# pcie2usbc.net
KiCad netlist of a schematic drawn in EAGLE
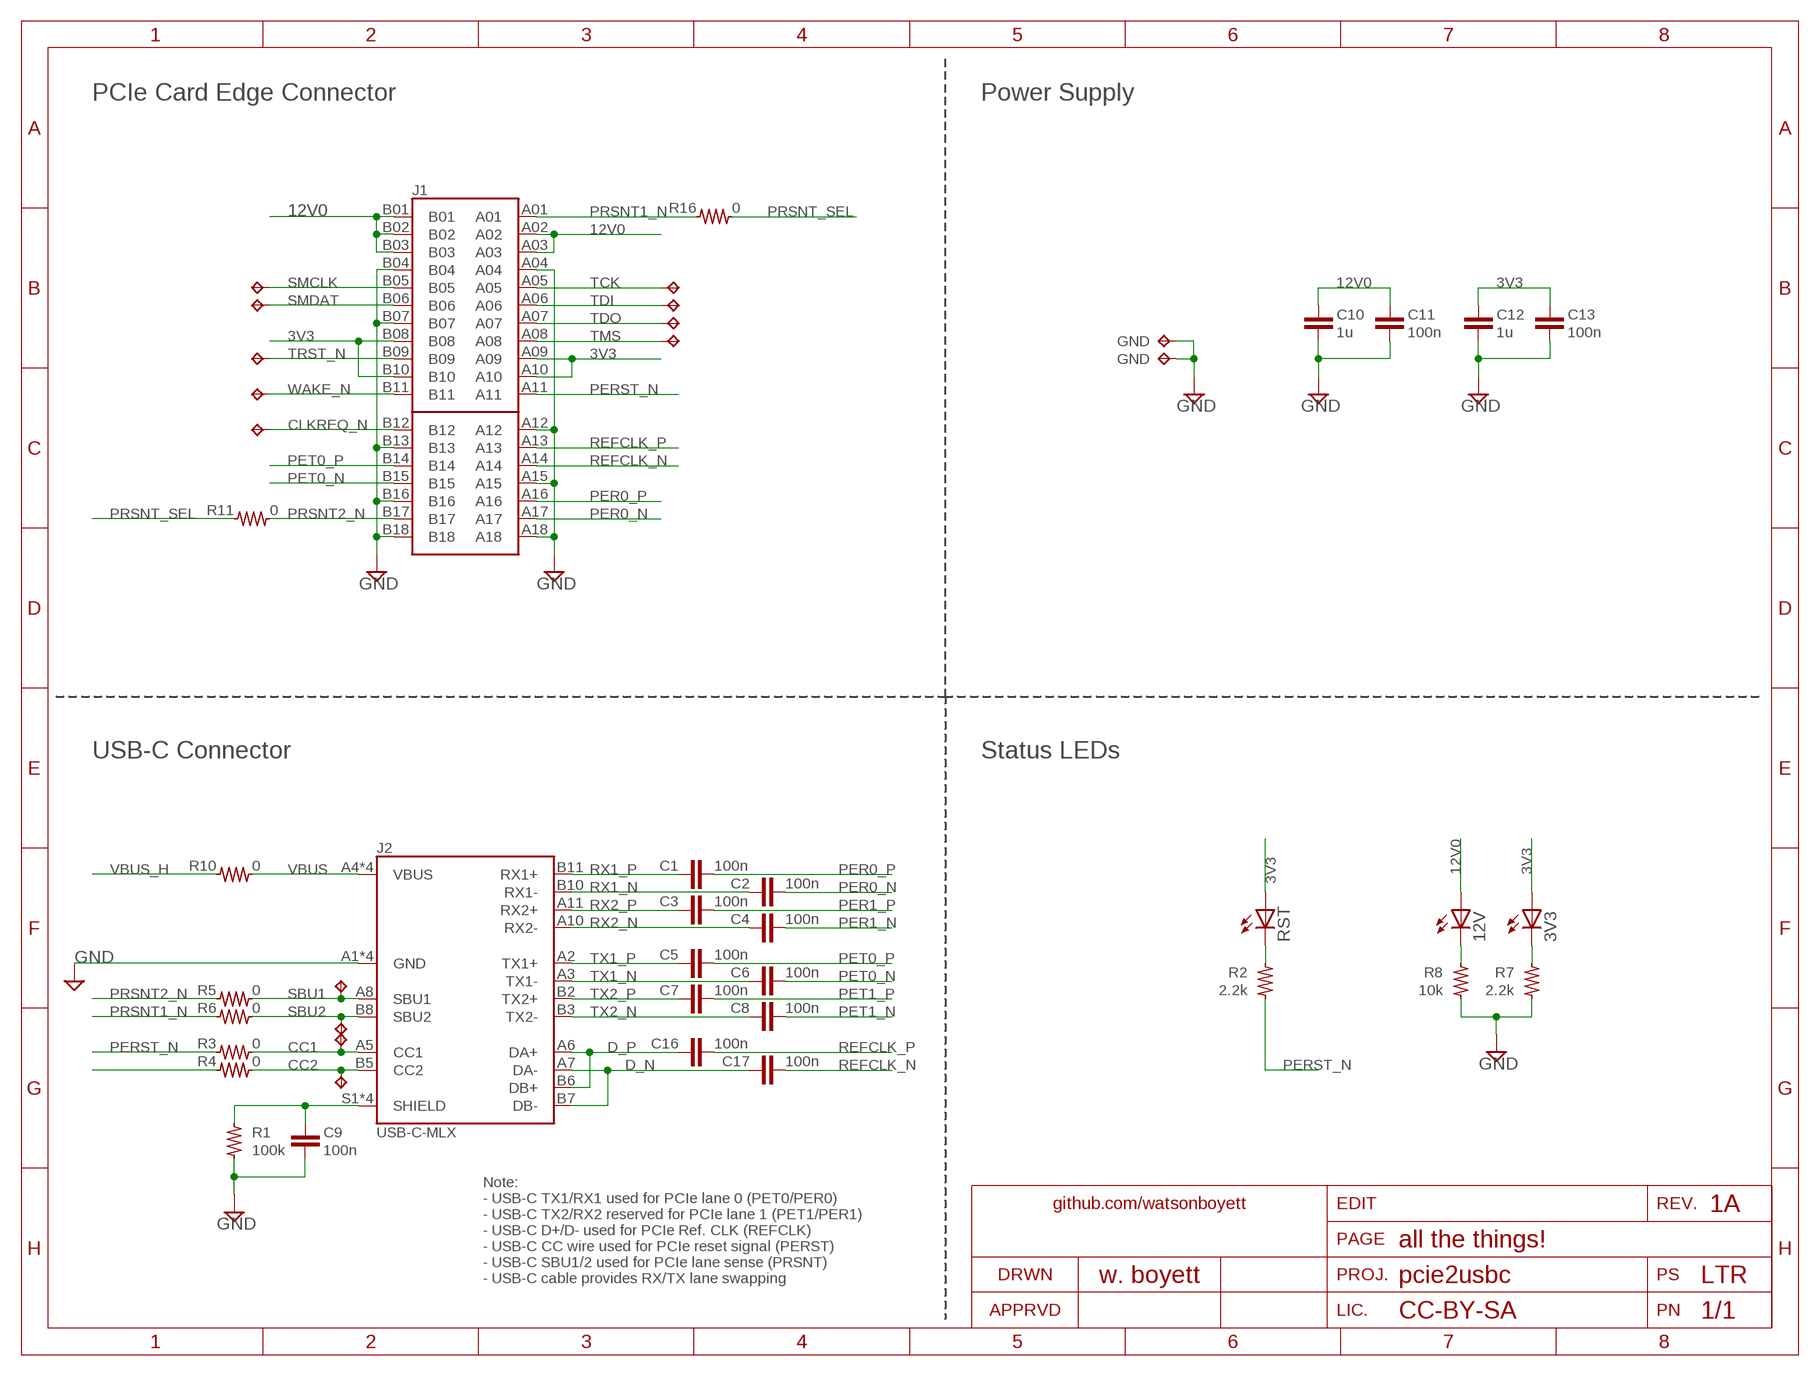
[diagram p0: schematic, sheet 1]

(export (version "E")
  (design (tool "Eeschema 10.0.6"))
  (components
    (comp (ref "3V3")
      (value "LEDSML0805")
      (footprint "eagle-import:SML0805")
      (libsource (lib "eagle-import") (part "LEDSML0805"))
    )
    (comp (ref "12V")
      (value "LEDSML0805")
      (footprint "eagle-import:SML0805")
      (libsource (lib "eagle-import") (part "LEDSML0805"))
    )
    (comp (ref "C1")
      (value "100n")
      (footprint "eagle-import:C0402")
      (libsource (lib "eagle-import") (part "C-EUC0402"))
    )
    (comp (ref "C2")
      (value "100n")
      (footprint "eagle-import:C0402")
      (libsource (lib "eagle-import") (part "C-EUC0402"))
    )
    (comp (ref "C3")
      (value "100n")
      (footprint "eagle-import:C0402")
      (libsource (lib "eagle-import") (part "C-EUC0402"))
    )
    (comp (ref "C4")
      (value "100n")
      (footprint "eagle-import:C0402")
      (libsource (lib "eagle-import") (part "C-EUC0402"))
    )
    (comp (ref "C5")
      (value "100n")
      (footprint "eagle-import:C0402")
      (libsource (lib "eagle-import") (part "C-EUC0402"))
    )
    (comp (ref "C6")
      (value "100n")
      (footprint "eagle-import:C0402")
      (libsource (lib "eagle-import") (part "C-EUC0402"))
    )
    (comp (ref "C7")
      (value "100n")
      (footprint "eagle-import:C0402")
      (libsource (lib "eagle-import") (part "C-EUC0402"))
    )
    (comp (ref "C8")
      (value "100n")
      (footprint "eagle-import:C0402")
      (libsource (lib "eagle-import") (part "C-EUC0402"))
    )
    (comp (ref "C9")
      (value "100n")
      (footprint "eagle-import:C0603K")
      (description "CAP CER 0.1UF 25V X7R 0603")
      (fields
        (field (name "MFG") "Yageo")
        (field (name "MPN") "CC0603KRX7R8BB104")
        (field (name "PN-DK") "311-1341-1-ND")
      )
      (libsource (lib "eagle-import") (part "C-EUC0603K"))
    )
    (comp (ref "C10")
      (value "1u")
      (footprint "eagle-import:C0603K")
      (description "CAP CER 0.1UF 25V X7R 0603")
      (fields
        (field (name "MFG") "Yageo")
        (field (name "MPN") "CC0603KRX7R8BB104")
        (field (name "PN-DK") "311-1341-1-ND")
      )
      (libsource (lib "eagle-import") (part "C-EUC0603K"))
    )
    (comp (ref "C11")
      (value "100n")
      (footprint "eagle-import:C0603K")
      (description "CAP CER 0.1UF 25V X7R 0603")
      (fields
        (field (name "MFG") "Yageo")
        (field (name "MPN") "CC0603KRX7R8BB104")
        (field (name "PN-DK") "311-1341-1-ND")
      )
      (libsource (lib "eagle-import") (part "C-EUC0603K"))
    )
    (comp (ref "C12")
      (value "1u")
      (footprint "eagle-import:C0603K")
      (description "CAP CER 0.1UF 25V X7R 0603")
      (fields
        (field (name "MFG") "Yageo")
        (field (name "MPN") "CC0603KRX7R8BB104")
        (field (name "PN-DK") "311-1341-1-ND")
      )
      (libsource (lib "eagle-import") (part "C-EUC0603K"))
    )
    (comp (ref "C13")
      (value "100n")
      (footprint "eagle-import:C0603K")
      (description "CAP CER 0.1UF 25V X7R 0603")
      (fields
        (field (name "MFG") "Yageo")
        (field (name "MPN") "CC0603KRX7R8BB104")
        (field (name "PN-DK") "311-1341-1-ND")
      )
      (libsource (lib "eagle-import") (part "C-EUC0603K"))
    )
    (comp (ref "C16")
      (value "100n")
      (footprint "eagle-import:C0402")
      (libsource (lib "eagle-import") (part "C-EUC0402"))
    )
    (comp (ref "C17")
      (value "100n")
      (footprint "eagle-import:C0402")
      (libsource (lib "eagle-import") (part "C-EUC0402"))
    )
    (comp (ref "J1")
      (value "PCIE-036-02-X-D-EMS2")
      (footprint "eagle-import:SAMTEC_PCIE-036-02-X-D-EMS2")
      (fields (field (name "MANUFACTURER") "Samtec"))
      (libsource (lib "eagle-import") (part "PCIE-036-02-X-D-EMS2"))
    )
    (comp (ref "J2")
      (value "USB-C-MLX")
      (footprint "eagle-import:MOLEX_105450-0101")
      (fields (field (name "MFG") "Molex") (field (name "MPN") "1054500101"))
      (libsource (lib "eagle-import") (part "USB-C-MLX"))
    )
    (comp (ref "R1")
      (value "100k")
      (footprint "eagle-import:R0603")
      (description "RES SMD 100K OHM 1% 1/10W 0603")
      (fields
        (field (name "MFG") "Yageo")
        (field (name "MPN") "RC0603FR-07100KL")
        (field (name "PN-DK") "311-100KHRCT-ND")
      )
      (libsource (lib "eagle-import") (part "R-US_R0603"))
    )
    (comp (ref "R2")
      (value "2.2k")
      (footprint "eagle-import:R0603")
      (libsource (lib "eagle-import") (part "R-US_R0603"))
    )
    (comp (ref "R3")
      (value "0")
      (footprint "eagle-import:R0603")
      (libsource (lib "eagle-import") (part "R-US_R0603"))
    )
    (comp (ref "R4")
      (value "0")
      (footprint "eagle-import:R0603")
      (libsource (lib "eagle-import") (part "R-US_R0603"))
    )
    (comp (ref "R5")
      (value "0")
      (footprint "eagle-import:R0603")
      (libsource (lib "eagle-import") (part "R-US_R0603"))
    )
    (comp (ref "R6")
      (value "0")
      (footprint "eagle-import:R0603")
      (libsource (lib "eagle-import") (part "R-US_R0603"))
    )
    (comp (ref "R7")
      (value "2.2k")
      (footprint "eagle-import:R0603")
      (libsource (lib "eagle-import") (part "R-US_R0603"))
    )
    (comp (ref "R8")
      (value "10k")
      (footprint "eagle-import:R0603")
      (libsource (lib "eagle-import") (part "R-US_R0603"))
    )
    (comp (ref "R10")
      (value "0")
      (footprint "eagle-import:R0603")
      (libsource (lib "eagle-import") (part "R-US_R0603"))
    )
    (comp (ref "R11")
      (value "0")
      (footprint "eagle-import:R0603")
      (libsource (lib "eagle-import") (part "R-US_R0603"))
    )
    (comp (ref "R16")
      (value "0")
      (footprint "eagle-import:R0603")
      (libsource (lib "eagle-import") (part "R-US_R0603"))
    )
    (comp (ref "RST")
      (value "LEDSML0805")
      (footprint "eagle-import:SML0805")
      (libsource (lib "eagle-import") (part "LEDSML0805"))
    )
    (comp (ref "TP1")
      (value "TPB0,635")
      (footprint "eagle-import:B0,635")
      (libsource (lib "eagle-import") (part "TPB0,635"))
    )
    (comp (ref "TP2")
      (value "TPB0,635")
      (footprint "eagle-import:B0,635")
      (libsource (lib "eagle-import") (part "TPB0,635"))
    )
    (comp (ref "TP3")
      (value "TPB0,635")
      (footprint "eagle-import:B0,635")
      (libsource (lib "eagle-import") (part "TPB0,635"))
    )
    (comp (ref "TP4")
      (value "TPB0,635")
      (footprint "eagle-import:B0,635")
      (libsource (lib "eagle-import") (part "TPB0,635"))
    )
    (comp (ref "TP5")
      (value "TPB0,635")
      (footprint "eagle-import:B0,635")
      (libsource (lib "eagle-import") (part "TPB0,635"))
    )
    (comp (ref "TP6")
      (value "TPB0,635")
      (footprint "eagle-import:B0,635")
      (libsource (lib "eagle-import") (part "TPB0,635"))
    )
    (comp (ref "TP7")
      (value "TPB0,635")
      (footprint "eagle-import:B0,635")
      (libsource (lib "eagle-import") (part "TPB0,635"))
    )
    (comp (ref "TP8")
      (value "TPB0,635")
      (footprint "eagle-import:B0,635")
      (libsource (lib "eagle-import") (part "TPB0,635"))
    )
    (comp (ref "TP9")
      (value "TPB0,635")
      (footprint "eagle-import:B0,635")
      (libsource (lib "eagle-import") (part "TPB0,635"))
    )
    (comp (ref "TP10")
      (value "TPTP38X20")
      (footprint "eagle-import:TP38X20")
      (fields
        (field (name "MFG") "Keystone Electronics")
        (field (name "MPN") "5019")
        (field (name "TP_SIGNAL_NAME") "GND")
      )
      (libsource (lib "eagle-import") (part "TPTP38X20"))
    )
    (comp (ref "TP11")
      (value "TPB0,635")
      (footprint "eagle-import:B0,635")
      (libsource (lib "eagle-import") (part "TPB0,635"))
    )
    (comp (ref "TP12")
      (value "TPB0,635")
      (footprint "eagle-import:B0,635")
      (libsource (lib "eagle-import") (part "TPB0,635"))
    )
    (comp (ref "TP13")
      (value "TPTP38X20")
      (footprint "eagle-import:TP38X20")
      (fields
        (field (name "MFG") "Keystone Electronics")
        (field (name "MPN") "5019")
        (field (name "TP_SIGNAL_NAME") "GND")
      )
      (libsource (lib "eagle-import") (part "TPTP38X20"))
    )
    (comp (ref "TP16")
      (value "TPB0,635")
      (footprint "eagle-import:B0,635")
      (libsource (lib "eagle-import") (part "TPB0,635"))
    )
    (comp (ref "TP21")
      (value "TPB0,635")
      (footprint "eagle-import:B0,635")
      (libsource (lib "eagle-import") (part "TPB0,635"))
    )
  )
  (nets
    (net (code "1") (name "/3V3") (class "Default")
      (node (ref "3V3") (pin "A") (pinfunction "A_A") (pintype "passive"))
      (node (ref "C12") (pin "1") (pinfunction "1_1") (pintype "passive"))
      (node (ref "C13") (pin "1") (pinfunction "1_1") (pintype "passive"))
      (node (ref "J1") (pin "A09") (pinfunction "A09_A09") (pintype "passive"))
      (node (ref "J1") (pin "A10") (pinfunction "A10_A10") (pintype "passive"))
      (node (ref "J1") (pin "B08") (pinfunction "B08_B08") (pintype "passive"))
      (node (ref "J1") (pin "B10") (pinfunction "B10_B10") (pintype "passive"))
      (node (ref "RST") (pin "A") (pinfunction "A_A") (pintype "passive"))
    )
    (net (code "2") (name "/12V0") (class "Default")
      (node (ref "12V") (pin "A") (pinfunction "A_A") (pintype "passive"))
      (node (ref "C10") (pin "1") (pinfunction "1_1") (pintype "passive"))
      (node (ref "C11") (pin "1") (pinfunction "1_1") (pintype "passive"))
      (node (ref "J1") (pin "A02") (pinfunction "A02_A02") (pintype "passive"))
      (node (ref "J1") (pin "A03") (pinfunction "A03_A03") (pintype "passive"))
      (node (ref "J1") (pin "B01") (pinfunction "B01_B01") (pintype "passive"))
      (node (ref "J1") (pin "B02") (pinfunction "B02_B02") (pintype "passive"))
      (node (ref "J1") (pin "B03") (pinfunction "B03_B03") (pintype "passive"))
    )
    (net (code "3") (name "/CC1") (class "Default")
      (node (ref "J2") (pin "A5") (pinfunction "CC1_A5") (pintype "passive"))
      (node (ref "R3") (pin "2") (pinfunction "2_2") (pintype "passive"))
      (node (ref "TP21") (pin "TP") (pinfunction "TP_TP") (pintype "bidirectional"))
    )
    (net (code "4") (name "/CC2") (class "Default")
      (node (ref "J2") (pin "B5") (pinfunction "CC2_B5") (pintype "passive"))
      (node (ref "R4") (pin "1") (pinfunction "1_1") (pintype "passive"))
      (node (ref "TP16") (pin "TP") (pinfunction "TP_TP") (pintype "bidirectional"))
    )
    (net (code "5") (name "/CLKREQ_N") (class "Default")
      (node (ref "J1") (pin "B12") (pinfunction "B12_B12") (pintype "passive"))
      (node (ref "TP9") (pin "TP") (pinfunction "TP_TP") (pintype "bidirectional"))
    )
    (net (code "6") (name "/D_N") (class "Default")
      (node (ref "C17") (pin "1") (pinfunction "1_1") (pintype "passive"))
      (node (ref "J2") (pin "A7") (pinfunction "DA-_A7") (pintype "passive"))
      (node (ref "J2") (pin "B7") (pinfunction "DB-_B7") (pintype "passive"))
    )
    (net (code "7") (name "/D_P") (class "Default")
      (node (ref "C16") (pin "1") (pinfunction "1_1") (pintype "passive"))
      (node (ref "J2") (pin "A6") (pinfunction "DA+_A6") (pintype "passive"))
      (node (ref "J2") (pin "B6") (pinfunction "DB+_B6") (pintype "passive"))
    )
    (net (code "8") (name "/GND") (class "Default")
      (node (ref "C10") (pin "2") (pinfunction "2_2") (pintype "passive"))
      (node (ref "C11") (pin "2") (pinfunction "2_2") (pintype "passive"))
      (node (ref "C12") (pin "2") (pinfunction "2_2") (pintype "passive"))
      (node (ref "C13") (pin "2") (pinfunction "2_2") (pintype "passive"))
      (node (ref "C9") (pin "2") (pinfunction "2_2") (pintype "passive"))
      (node (ref "J1") (pin "A04") (pinfunction "A04_A04") (pintype "passive"))
      (node (ref "J1") (pin "A12") (pinfunction "A12_A12") (pintype "passive"))
      (node (ref "J1") (pin "A15") (pinfunction "A15_A15") (pintype "passive"))
      (node (ref "J1") (pin "A18") (pinfunction "A18_A18") (pintype "passive"))
      (node (ref "J1") (pin "B04") (pinfunction "B04_B04") (pintype "passive"))
      (node (ref "J1") (pin "B07") (pinfunction "B07_B07") (pintype "passive"))
      (node (ref "J1") (pin "B13") (pinfunction "B13_B13") (pintype "passive"))
      (node (ref "J1") (pin "B16") (pinfunction "B16_B16") (pintype "passive"))
      (node (ref "J1") (pin "B18") (pinfunction "B18_B18") (pintype "passive"))
      (node (ref "J2") (pin "A1") (pinfunction "GND_A1") (pintype "passive"))
      (node (ref "J2") (pin "A12") (pinfunction "GND_A12") (pintype "passive"))
      (node (ref "J2") (pin "B1") (pinfunction "GND_B1") (pintype "passive"))
      (node (ref "J2") (pin "B12") (pinfunction "GND_B12") (pintype "passive"))
      (node (ref "R1") (pin "1") (pinfunction "1_1") (pintype "passive"))
      (node (ref "R7") (pin "1") (pinfunction "1_1") (pintype "passive"))
      (node (ref "R8") (pin "1") (pinfunction "1_1") (pintype "passive"))
      (node (ref "TP10") (pin "TP") (pinfunction "TP_TP") (pintype "bidirectional"))
      (node (ref "TP13") (pin "TP") (pinfunction "TP_TP") (pintype "bidirectional"))
    )
    (net (code "9") (name "/PER0_N") (class "Default")
      (node (ref "C2") (pin "2") (pinfunction "2_2") (pintype "passive"))
      (node (ref "J1") (pin "A17") (pinfunction "A17_A17") (pintype "passive"))
    )
    (net (code "10") (name "/PER0_P") (class "Default")
      (node (ref "C1") (pin "2") (pinfunction "2_2") (pintype "passive"))
      (node (ref "J1") (pin "A16") (pinfunction "A16_A16") (pintype "passive"))
    )
    (net (code "11") (name "/PER1_N") (class "Default")
      (node (ref "C4") (pin "2") (pinfunction "2_2") (pintype "passive"))
    )
    (net (code "12") (name "/PER1_P") (class "Default")
      (node (ref "C3") (pin "2") (pinfunction "2_2") (pintype "passive"))
    )
    (net (code "13") (name "/PERST_N") (class "Default")
      (node (ref "J1") (pin "A11") (pinfunction "A11_A11") (pintype "passive"))
      (node (ref "R2") (pin "1") (pinfunction "1_1") (pintype "passive"))
      (node (ref "R3") (pin "1") (pinfunction "1_1") (pintype "passive"))
    )
    (net (code "14") (name "/PET0_N") (class "Default")
      (node (ref "C6") (pin "2") (pinfunction "2_2") (pintype "passive"))
      (node (ref "J1") (pin "B15") (pinfunction "B15_B15") (pintype "passive"))
    )
    (net (code "15") (name "/PET0_P") (class "Default")
      (node (ref "C5") (pin "2") (pinfunction "2_2") (pintype "passive"))
      (node (ref "J1") (pin "B14") (pinfunction "B14_B14") (pintype "passive"))
    )
    (net (code "16") (name "/PET1_N") (class "Default")
      (node (ref "C8") (pin "2") (pinfunction "2_2") (pintype "passive"))
    )
    (net (code "17") (name "/PET1_P") (class "Default")
      (node (ref "C7") (pin "2") (pinfunction "2_2") (pintype "passive"))
    )
    (net (code "18") (name "/PRSNT1_N") (class "Default")
      (node (ref "J1") (pin "A01") (pinfunction "A01_A01") (pintype "passive"))
      (node (ref "R16") (pin "1") (pinfunction "1_1") (pintype "passive"))
      (node (ref "R6") (pin "1") (pinfunction "1_1") (pintype "passive"))
    )
    (net (code "19") (name "/PRSNT2_N") (class "Default")
      (node (ref "J1") (pin "B17") (pinfunction "B17_B17") (pintype "passive"))
      (node (ref "R11") (pin "2") (pinfunction "2_2") (pintype "passive"))
      (node (ref "R5") (pin "1") (pinfunction "1_1") (pintype "passive"))
    )
    (net (code "20") (name "/PRSNT_SEL") (class "Default")
      (node (ref "R11") (pin "1") (pinfunction "1_1") (pintype "passive"))
      (node (ref "R16") (pin "2") (pinfunction "2_2") (pintype "passive"))
    )
    (net (code "21") (name "/REFCLK_N") (class "Default")
      (node (ref "C17") (pin "2") (pinfunction "2_2") (pintype "passive"))
      (node (ref "J1") (pin "A14") (pinfunction "A14_A14") (pintype "passive"))
    )
    (net (code "22") (name "/REFCLK_P") (class "Default")
      (node (ref "C16") (pin "2") (pinfunction "2_2") (pintype "passive"))
      (node (ref "J1") (pin "A13") (pinfunction "A13_A13") (pintype "passive"))
    )
    (net (code "23") (name "/RX1_N") (class "Default")
      (node (ref "C2") (pin "1") (pinfunction "1_1") (pintype "passive"))
      (node (ref "J2") (pin "B10") (pinfunction "RX1-_B10") (pintype "passive"))
    )
    (net (code "24") (name "/RX1_P") (class "Default")
      (node (ref "C1") (pin "1") (pinfunction "1_1") (pintype "passive"))
      (node (ref "J2") (pin "B11") (pinfunction "RX1+_B11") (pintype "passive"))
    )
    (net (code "25") (name "/RX2_N") (class "Default")
      (node (ref "C4") (pin "1") (pinfunction "1_1") (pintype "passive"))
      (node (ref "J2") (pin "A10") (pinfunction "RX2-_A10") (pintype "passive"))
    )
    (net (code "26") (name "/RX2_P") (class "Default")
      (node (ref "C3") (pin "1") (pinfunction "1_1") (pintype "passive"))
      (node (ref "J2") (pin "A11") (pinfunction "RX2+_A11") (pintype "passive"))
    )
    (net (code "27") (name "/SBU1") (class "Default")
      (node (ref "J2") (pin "A8") (pinfunction "SBU1_A8") (pintype "passive"))
      (node (ref "R5") (pin "2") (pinfunction "2_2") (pintype "passive"))
      (node (ref "TP11") (pin "TP") (pinfunction "TP_TP") (pintype "bidirectional"))
    )
    (net (code "28") (name "/SBU2") (class "Default")
      (node (ref "J2") (pin "B8") (pinfunction "SBU2_B8") (pintype "passive"))
      (node (ref "R6") (pin "2") (pinfunction "2_2") (pintype "passive"))
      (node (ref "TP12") (pin "TP") (pinfunction "TP_TP") (pintype "bidirectional"))
    )
    (net (code "29") (name "/SMCLK") (class "Default")
      (node (ref "J1") (pin "B05") (pinfunction "B05_B05") (pintype "passive"))
      (node (ref "TP5") (pin "TP") (pinfunction "TP_TP") (pintype "bidirectional"))
    )
    (net (code "30") (name "/SMDAT") (class "Default")
      (node (ref "J1") (pin "B06") (pinfunction "B06_B06") (pintype "passive"))
      (node (ref "TP6") (pin "TP") (pinfunction "TP_TP") (pintype "bidirectional"))
    )
    (net (code "31") (name "/TCK") (class "Default")
      (node (ref "J1") (pin "A05") (pinfunction "A05_A05") (pintype "passive"))
      (node (ref "TP1") (pin "TP") (pinfunction "TP_TP") (pintype "bidirectional"))
    )
    (net (code "32") (name "/TDI") (class "Default")
      (node (ref "J1") (pin "A06") (pinfunction "A06_A06") (pintype "passive"))
      (node (ref "TP2") (pin "TP") (pinfunction "TP_TP") (pintype "bidirectional"))
    )
    (net (code "33") (name "/TDO") (class "Default")
      (node (ref "J1") (pin "A07") (pinfunction "A07_A07") (pintype "passive"))
      (node (ref "TP3") (pin "TP") (pinfunction "TP_TP") (pintype "bidirectional"))
    )
    (net (code "34") (name "/TMS") (class "Default")
      (node (ref "J1") (pin "A08") (pinfunction "A08_A08") (pintype "passive"))
      (node (ref "TP4") (pin "TP") (pinfunction "TP_TP") (pintype "bidirectional"))
    )
    (net (code "35") (name "/TRST_N") (class "Default")
      (node (ref "J1") (pin "B09") (pinfunction "B09_B09") (pintype "passive"))
      (node (ref "TP7") (pin "TP") (pinfunction "TP_TP") (pintype "bidirectional"))
    )
    (net (code "36") (name "/TX1_N") (class "Default")
      (node (ref "C6") (pin "1") (pinfunction "1_1") (pintype "passive"))
      (node (ref "J2") (pin "A3") (pinfunction "TX1-_A3") (pintype "passive"))
    )
    (net (code "37") (name "/TX1_P") (class "Default")
      (node (ref "C5") (pin "1") (pinfunction "1_1") (pintype "passive"))
      (node (ref "J2") (pin "A2") (pinfunction "TX1+_A2") (pintype "passive"))
    )
    (net (code "38") (name "/TX2_N") (class "Default")
      (node (ref "C8") (pin "1") (pinfunction "1_1") (pintype "passive"))
      (node (ref "J2") (pin "B3") (pinfunction "TX2-_B3") (pintype "passive"))
    )
    (net (code "39") (name "/TX2_P") (class "Default")
      (node (ref "C7") (pin "1") (pinfunction "1_1") (pintype "passive"))
      (node (ref "J2") (pin "B2") (pinfunction "TX2+_B2") (pintype "passive"))
    )
    (net (code "40") (name "/VBUS") (class "Default")
      (node (ref "J2") (pin "A4") (pinfunction "VBUS_A4") (pintype "passive"))
      (node (ref "J2") (pin "A9") (pinfunction "VBUS_A9") (pintype "passive"))
      (node (ref "J2") (pin "B4") (pinfunction "VBUS_B4") (pintype "passive"))
      (node (ref "J2") (pin "B9") (pinfunction "VBUS_B9") (pintype "passive"))
      (node (ref "R10") (pin "2") (pinfunction "2_2") (pintype "passive"))
    )
    (net (code "41") (name "/VBUS_H") (class "Default")
      (node (ref "R10") (pin "1") (pinfunction "1_1") (pintype "passive"))
    )
    (net (code "42") (name "/WAKE_N") (class "Default")
      (node (ref "J1") (pin "B11") (pinfunction "B11_B11") (pintype "passive"))
      (node (ref "TP8") (pin "TP") (pinfunction "TP_TP") (pintype "bidirectional"))
    )
    (net (code "43") (name "Net-(3V3-PadC)") (class "Default")
      (node (ref "3V3") (pin "C") (pinfunction "C_C") (pintype "passive"))
      (node (ref "R7") (pin "2") (pinfunction "2_2") (pintype "passive"))
    )
    (net (code "44") (name "Net-(12V-PadC)") (class "Default")
      (node (ref "12V") (pin "C") (pinfunction "C_C") (pintype "passive"))
      (node (ref "R8") (pin "2") (pinfunction "2_2") (pintype "passive"))
    )
    (net (code "45") (name "Net-(C9-Pad1)") (class "Default")
      (node (ref "C9") (pin "1") (pinfunction "1_1") (pintype "passive"))
      (node (ref "J2") (pin "S1") (pinfunction "SHIELD_S1") (pintype "passive"))
      (node (ref "J2") (pin "S2") (pinfunction "SHIELD_S2") (pintype "passive"))
      (node (ref "J2") (pin "S3") (pinfunction "SHIELD_S3") (pintype "passive"))
      (node (ref "J2") (pin "S4") (pinfunction "SHIELD_S4") (pintype "passive"))
      (node (ref "R1") (pin "2") (pinfunction "2_2") (pintype "passive"))
    )
    (net (code "46") (name "Net-(R2-Pad2)") (class "Default")
      (node (ref "R2") (pin "2") (pinfunction "2_2") (pintype "passive"))
      (node (ref "RST") (pin "C") (pinfunction "C_C") (pintype "passive"))
    )
    (net (code "47") (name "unconnected-(R4-Pad2)") (class "Default")
      (node (ref "R4") (pin "2") (pinfunction "2_2") (pintype "passive"))
    )
  )
)
